# ProPrj_Pico_Pi_W_2024-12-25.net
KiCad netlist of a schematic drawn in EasyEDA Pro
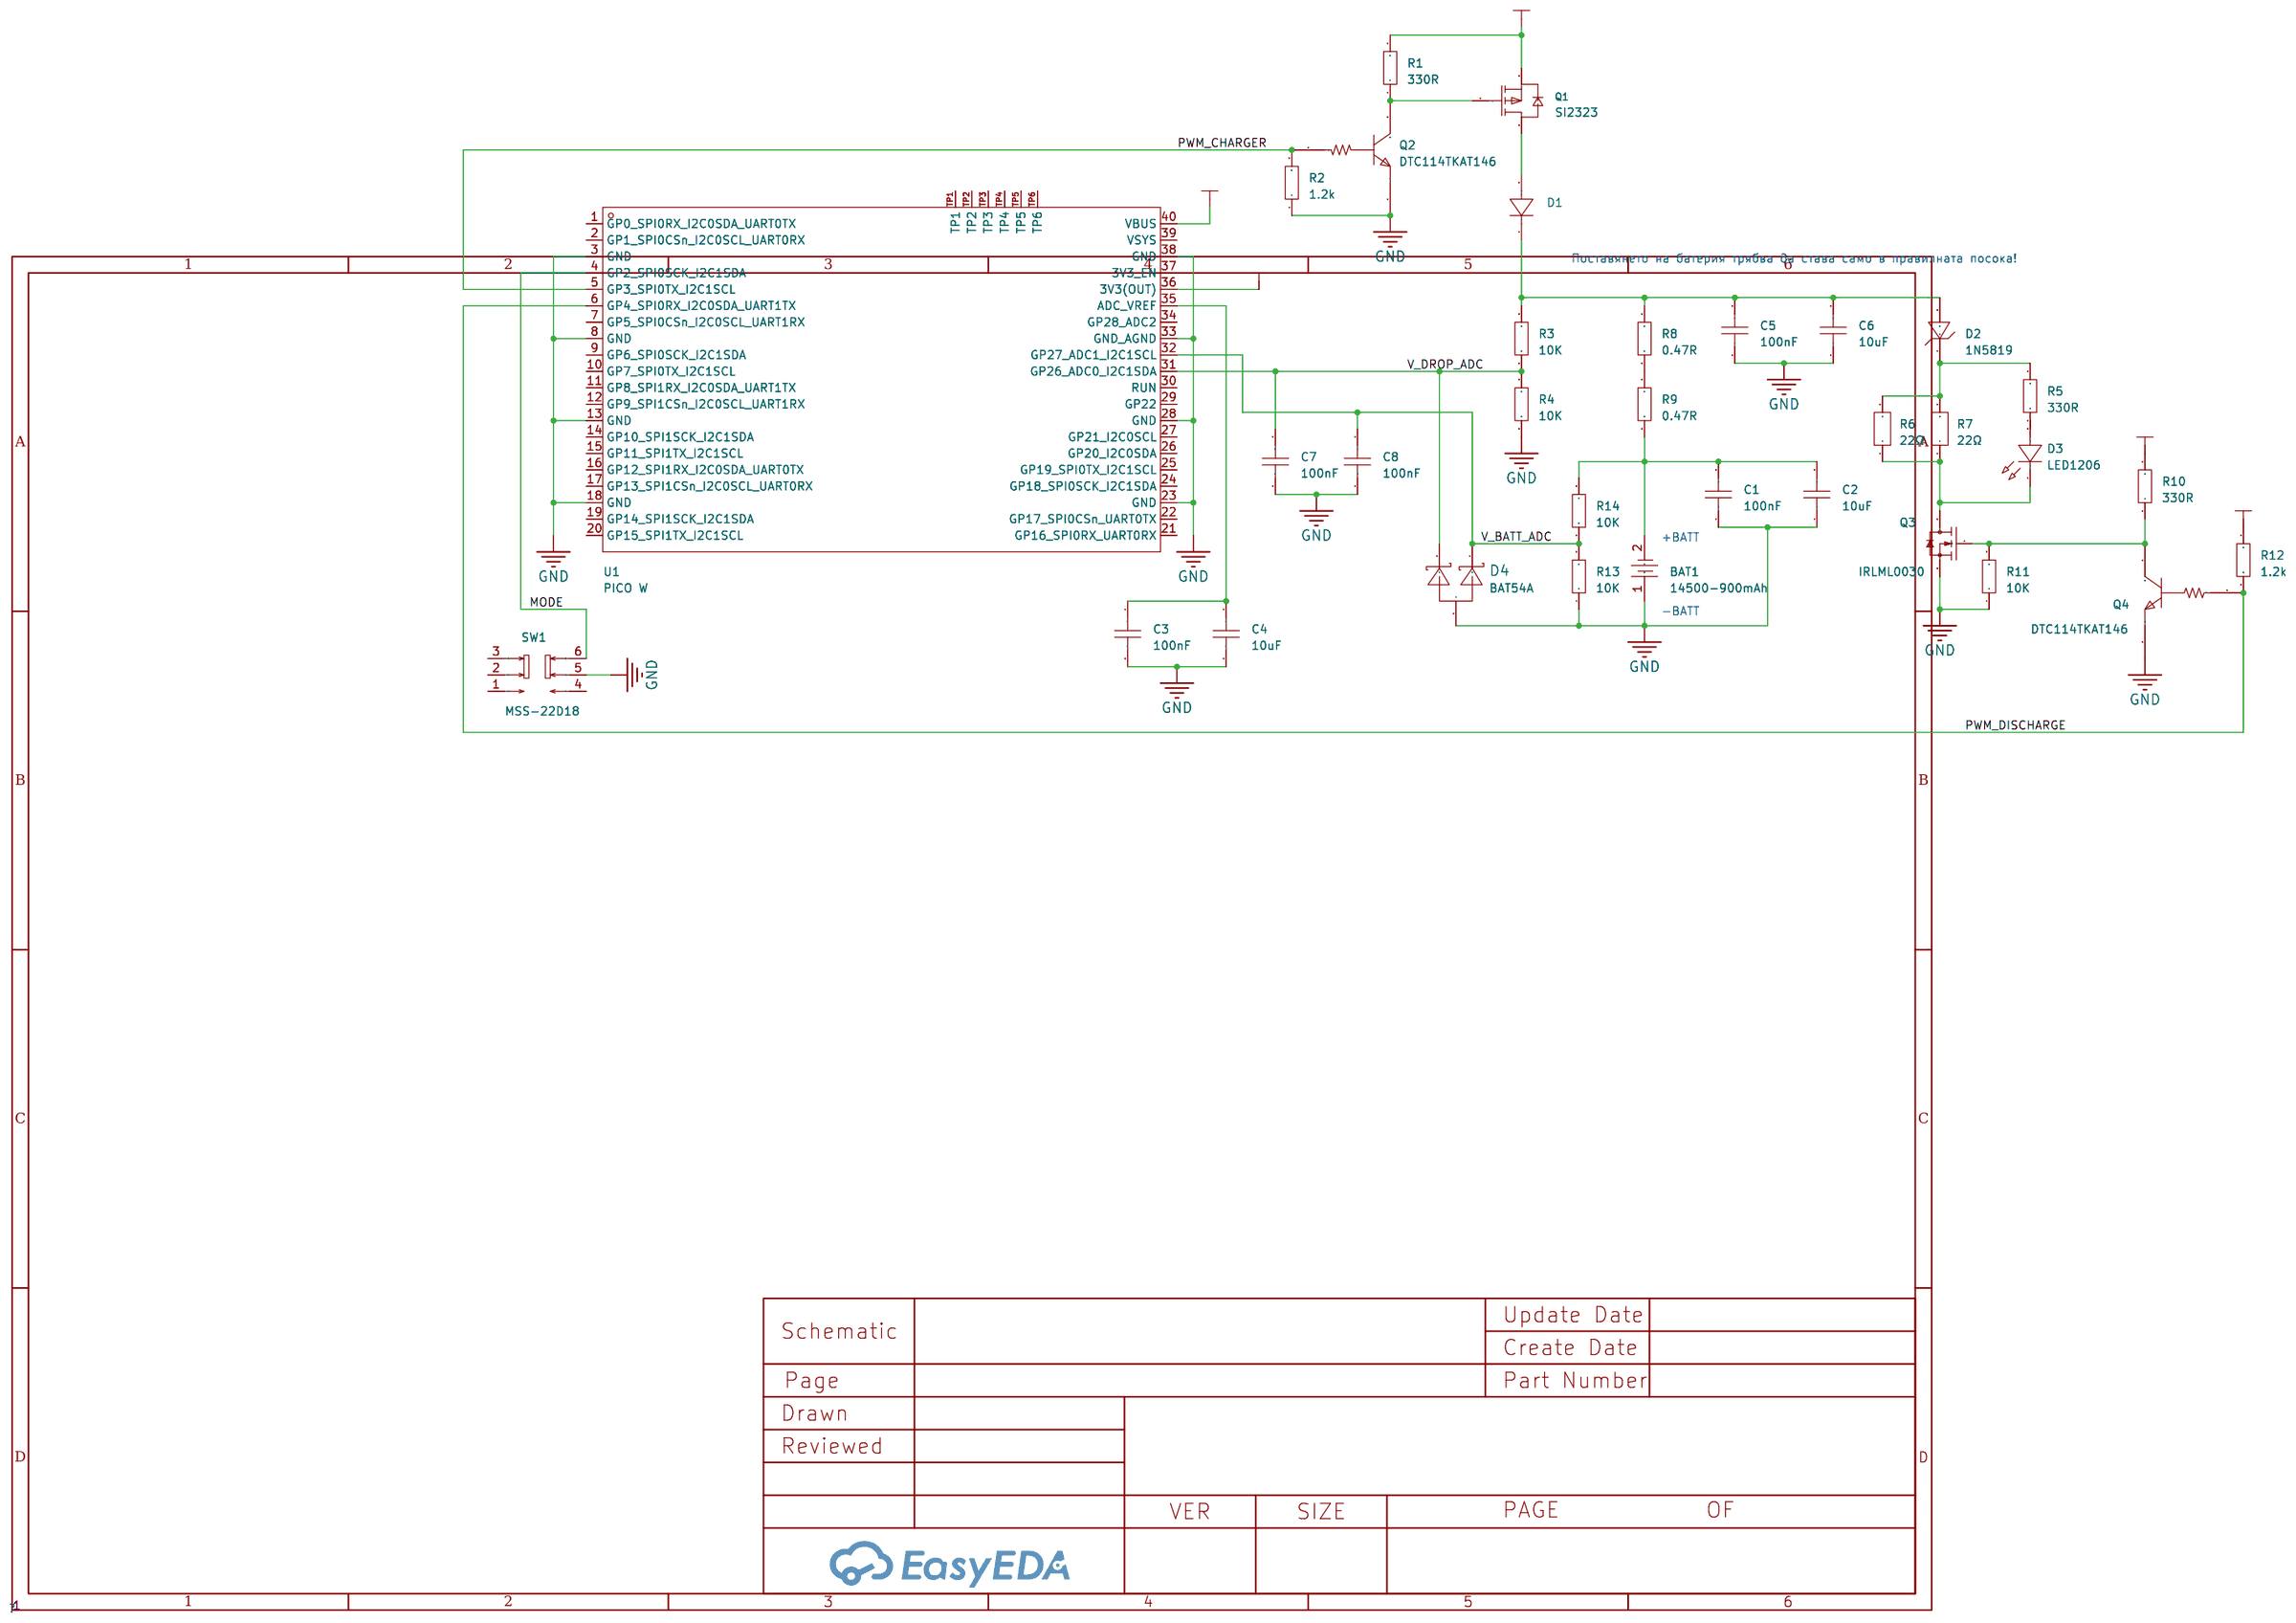
[diagram p0: schematic sheet]

(export (version "E")
  (design (tool "Eeschema 10.0.6"))
  (components
    (comp (ref "BAT1")
      (value "14500-900mAh")
      (footprint "easyedapro:BAT-TH_FLY-ER14250-1200MAH-01")
      (fields (field (name "Manufacturer") "FLYOUNG(远阳)"))
      (libsource (lib "easyedapro") (part "FLY-ER14250-1200MAH-01"))
    )
    (comp (ref "C1")
      (value "100nF")
      (footprint "easyedapro:C0805")
      (libsource (lib "easyedapro") (part "CAP"))
    )
    (comp (ref "C2")
      (value "10uF")
      (footprint "easyedapro:C0805")
      (libsource (lib "easyedapro") (part "CAP"))
    )
    (comp (ref "C3")
      (value "100nF")
      (footprint "easyedapro:C0805")
      (libsource (lib "easyedapro") (part "CAP"))
    )
    (comp (ref "C4")
      (value "10uF")
      (footprint "easyedapro:C0805")
      (libsource (lib "easyedapro") (part "CAP"))
    )
    (comp (ref "C5")
      (value "100nF")
      (footprint "easyedapro:C0805")
      (libsource (lib "easyedapro") (part "CAP"))
    )
    (comp (ref "C6")
      (value "10uF")
      (footprint "easyedapro:C0805")
      (libsource (lib "easyedapro") (part "CAP"))
    )
    (comp (ref "C7")
      (value "100nF")
      (footprint "easyedapro:C0805")
      (libsource (lib "easyedapro") (part "CAP"))
    )
    (comp (ref "C8")
      (value "100nF")
      (footprint "easyedapro:C0805")
      (libsource (lib "easyedapro") (part "CAP"))
    )
    (comp (ref "D1")
      (value "~")
      (footprint "easyedapro:SMA_L4.4-W2.8-LS5.4-RD")
      (libsource (lib "easyedapro") (part "D_1N4007"))
    )
    (comp (ref "D2")
      (value "1N5819")
      (footprint "easyedapro:DO-41_BD2.4-L4.7-P8.70-D0.9-RD")
      (description "Forward Voltage (Vf@If):600mV@1A Reverse Voltage (Vr):40V Average Rectified Current (Io):1A")
      (fields (field (name "Manufacturer") "银河微电子"))
      (libsource (lib "easyedapro") (part "1N5819_C393567"))
    )
    (comp (ref "D3")
      (value "LED1206")
      (footprint "easyedapro:LED1206-RD")
      (libsource (lib "easyedapro") (part "LED1206"))
    )
    (comp (ref "D4")
      (value "BAT54A")
      (footprint "easyedapro:SOT-23-3_L2.9-W1.3-P1.90-LS2.4-BR")
      (description "Forward Voltage (Vf@If):800mV@100mA Reverse Voltage (Vr):30V Average Rectified Current (Io):200mA")
      (fields (field (name "Manufacturer") "HT(金誉)"))
      (libsource (lib "easyedapro") (part "BAT54A_C179724"))
    )
    (comp (ref "Q1")
      (value "SI2323")
      (footprint "easyedapro:SOT-23-3_L2.9-W1.3-P0.95-LS2.4-BR")
      (fields (field (name "Manufacturer") "PAKER(派克微)"))
      (libsource (lib "easyedapro") (part "SI2323"))
    )
    (comp (ref "Q2")
      (value "DTC114TKAT146")
      (footprint "easyedapro:SOT-346_L2.9-W1.6-P1.90-LS2.8-TR-CW")
      (fields (field (name "Manufacturer") "ROHM(罗姆)"))
      (libsource (lib "easyedapro") (part "DTC114TKAT146"))
    )
    (comp (ref "Q3")
      (value "IRLML0030")
      (footprint "easyedapro:SOT-23-3_L2.9-W1.3-P1.90-LS2.4-BR")
      (fields (field (name "Manufacturer") "Leiditech(雷卯电子)"))
      (libsource (lib "easyedapro") (part "IRLML0030"))
    )
    (comp (ref "Q4")
      (value "DTC114TKAT146")
      (footprint "easyedapro:SOT-346_L2.9-W1.6-P1.90-LS2.8-TR-CW")
      (fields (field (name "Manufacturer") "ROHM(罗姆)"))
      (libsource (lib "easyedapro") (part "DTC114TKAT146"))
    )
    (comp (ref "R1")
      (value "330R")
      (footprint "easyedapro:R0603")
      (libsource (lib "easyedapro") (part "Res"))
    )
    (comp (ref "R2")
      (value "1.2k")
      (footprint "easyedapro:R0603")
      (libsource (lib "easyedapro") (part "Res"))
    )
    (comp (ref "R3") (value "10K") (footprint "easyedapro:R0603") (libsource (lib "easyedapro") (part "Res")))
    (comp (ref "R4") (value "10K") (footprint "easyedapro:R0603") (libsource (lib "easyedapro") (part "Res")))
    (comp (ref "R5")
      (value "330R")
      (footprint "easyedapro:R0603")
      (libsource (lib "easyedapro") (part "Res"))
    )
    (comp (ref "R6")
      (value "22Ω")
      (footprint "easyedapro:RES-TH_BD8.5-L24.5-P28.5-D0.7")
      (fields (field (name "Manufacturer Part") "FKN500JR-91-15R") (field (name "Manufacturer") "YAGEO(国巨)"))
      (libsource (lib "easyedapro") (part "FKN500JR-91-15R"))
    )
    (comp (ref "R7")
      (value "22Ω")
      (footprint "easyedapro:RES-TH_BD8.5-L24.5-P28.5-D0.7")
      (fields (field (name "Manufacturer Part") "FKN500JR-91-15R") (field (name "Manufacturer") "YAGEO(国巨)"))
      (libsource (lib "easyedapro") (part "FKN500JR-91-15R"))
    )
    (comp (ref "R8")
      (value "0.47R")
      (footprint "easyedapro:R0603")
      (libsource (lib "easyedapro") (part "Res"))
    )
    (comp (ref "R9")
      (value "0.47R")
      (footprint "easyedapro:R0603")
      (libsource (lib "easyedapro") (part "Res"))
    )
    (comp (ref "R10")
      (value "330R")
      (footprint "easyedapro:R0603")
      (libsource (lib "easyedapro") (part "Res"))
    )
    (comp (ref "R11")
      (value "10K")
      (footprint "easyedapro:R0603")
      (libsource (lib "easyedapro") (part "Res"))
    )
    (comp (ref "R12")
      (value "1.2k")
      (footprint "easyedapro:R0603")
      (libsource (lib "easyedapro") (part "Res"))
    )
    (comp (ref "R13")
      (value "10K")
      (footprint "easyedapro:R0603")
      (libsource (lib "easyedapro") (part "Res"))
    )
    (comp (ref "R14")
      (value "10K")
      (footprint "easyedapro:R0603")
      (libsource (lib "easyedapro") (part "Res"))
    )
    (comp (ref "SW1")
      (value "MSS-22D18")
      (footprint "easyedapro:SW-TH_MSS-22D18")
      (libsource (lib "easyedapro") (part "MSS-22D18(杆长2MM)"))
    )
    (comp (ref "U1")
      (value "PICO W")
      (footprint "easyedapro:COMM-SMD_L51.0-W21.0-P2.54_PICOW")
      (fields (field (name "Manufacturer") "Raspberry Pi(树莓派)"))
      (libsource (lib "easyedapro") (part "PICO W"))
    )
  )
  (nets
    (net (code "1") (name "+3V") (class "Default")
      (node (ref "R12") (pin "2") (pinfunction "2_2") (pintype "input"))
      (node (ref "U1") (pin "36") (pinfunction "3V3(OUT)_36") (pintype "unspecified"))
    )
    (net (code "2") (name "+5V") (class "Default")
      (node (ref "Q1") (pin "2") (pinfunction "S_2") (pintype "input"))
      (node (ref "R1") (pin "2") (pinfunction "2_2") (pintype "input"))
      (node (ref "R10") (pin "2") (pinfunction "2_2") (pintype "input"))
      (node (ref "U1") (pin "40") (pinfunction "VBUS_40") (pintype "unspecified"))
    )
    (net (code "3") (name "/MODE") (class "Default")
      (node (ref "SW1") (pin "6") (pinfunction "6_6") (pintype "unspecified"))
      (node (ref "U1") (pin "4") (pinfunction "GP2_SPI0SCK_I2C1SDA_4") (pintype "unspecified"))
    )
    (net (code "4") (name "/PWM_CHARGER") (class "Default")
      (node (ref "Q2") (pin "2") (pinfunction "B_2") (pintype "unspecified"))
      (node (ref "R2") (pin "2") (pinfunction "2_2") (pintype "input"))
      (node (ref "U1") (pin "5") (pinfunction "GP3_SPI0TX_I2C1SCL_5") (pintype "unspecified"))
    )
    (net (code "5") (name "/PWM_DISCHARGE") (class "Default")
      (node (ref "Q4") (pin "2") (pinfunction "B_2") (pintype "unspecified"))
      (node (ref "R12") (pin "1") (pinfunction "1_1") (pintype "input"))
      (node (ref "U1") (pin "6") (pinfunction "GP4_SPI0RX_I2C0SDA_UART1TX_6") (pintype "unspecified"))
    )
    (net (code "6") (name "/V_BATT_ADC") (class "Default")
      (node (ref "C8") (pin "2") (pinfunction "2_2") (pintype "input"))
      (node (ref "D4") (pin "1") (pinfunction "A_1") (pintype "input"))
      (node (ref "R13") (pin "2") (pinfunction "2_2") (pintype "input"))
      (node (ref "R14") (pin "1") (pinfunction "1_1") (pintype "input"))
      (node (ref "U1") (pin "32") (pinfunction "GP27_ADC1_I2C1SCL_32") (pintype "unspecified"))
    )
    (net (code "7") (name "/V_DROP_ADC") (class "Default")
      (node (ref "C7") (pin "2") (pinfunction "2_2") (pintype "input"))
      (node (ref "D4") (pin "2") (pinfunction "A_2") (pintype "input"))
      (node (ref "R3") (pin "1") (pinfunction "1_1") (pintype "input"))
      (node (ref "R4") (pin "2") (pinfunction "2_2") (pintype "input"))
      (node (ref "U1") (pin "31") (pinfunction "GP26_ADC0_I2C1SDA_31") (pintype "unspecified"))
    )
    (net (code "8") (name "GND") (class "Default")
      (node (ref "BAT1") (pin "1") (pinfunction "1_1") (pintype "input"))
      (node (ref "C1") (pin "1") (pinfunction "1_1") (pintype "input"))
      (node (ref "C2") (pin "1") (pinfunction "1_1") (pintype "input"))
      (node (ref "C3") (pin "2") (pinfunction "2_2") (pintype "input"))
      (node (ref "C4") (pin "2") (pinfunction "2_2") (pintype "input"))
      (node (ref "C5") (pin "1") (pinfunction "1_1") (pintype "input"))
      (node (ref "C6") (pin "1") (pinfunction "1_1") (pintype "input"))
      (node (ref "C7") (pin "1") (pinfunction "1_1") (pintype "input"))
      (node (ref "C8") (pin "1") (pinfunction "1_1") (pintype "input"))
      (node (ref "D4") (pin "3") (pinfunction "K_3") (pintype "input"))
      (node (ref "Q2") (pin "1") (pinfunction "E_1") (pintype "unspecified"))
      (node (ref "Q3") (pin "2") (pinfunction "S_2") (pintype "unspecified"))
      (node (ref "Q4") (pin "1") (pinfunction "E_1") (pintype "unspecified"))
      (node (ref "R11") (pin "1") (pinfunction "1_1") (pintype "input"))
      (node (ref "R13") (pin "1") (pinfunction "1_1") (pintype "input"))
      (node (ref "R2") (pin "1") (pinfunction "1_1") (pintype "input"))
      (node (ref "R4") (pin "1") (pinfunction "1_1") (pintype "input"))
      (node (ref "SW1") (pin "5") (pinfunction "5_5") (pintype "unspecified"))
      (node (ref "U1") (pin "13") (pinfunction "GND_13") (pintype "unspecified"))
      (node (ref "U1") (pin "18") (pinfunction "GND_18") (pintype "unspecified"))
      (node (ref "U1") (pin "23") (pinfunction "GND_23") (pintype "unspecified"))
      (node (ref "U1") (pin "28") (pinfunction "GND_28") (pintype "unspecified"))
      (node (ref "U1") (pin "3") (pinfunction "GND_3") (pintype "unspecified"))
      (node (ref "U1") (pin "33") (pinfunction "GND_AGND_33") (pintype "unspecified"))
      (node (ref "U1") (pin "38") (pinfunction "GND_38") (pintype "unspecified"))
      (node (ref "U1") (pin "8") (pinfunction "GND_8") (pintype "unspecified"))
    )
    (net (code "9") (name "Net-(BAT1-Pad2)") (class "Default")
      (node (ref "BAT1") (pin "2") (pinfunction "2_2") (pintype "input"))
      (node (ref "C1") (pin "2") (pinfunction "2_2") (pintype "input"))
      (node (ref "C2") (pin "2") (pinfunction "2_2") (pintype "input"))
      (node (ref "R14") (pin "2") (pinfunction "2_2") (pintype "input"))
      (node (ref "R9") (pin "1") (pinfunction "1_1") (pintype "input"))
    )
    (net (code "10") (name "Net-(D1-A)") (class "Default")
      (node (ref "D1") (pin "2") (pinfunction "A_2") (pintype "input"))
      (node (ref "Q1") (pin "3") (pinfunction "D_3") (pintype "input"))
    )
    (net (code "11") (name "Net-(D1-K)") (class "Default")
      (node (ref "C5") (pin "2") (pinfunction "2_2") (pintype "input"))
      (node (ref "C6") (pin "2") (pinfunction "2_2") (pintype "input"))
      (node (ref "D1") (pin "1") (pinfunction "K_1") (pintype "input"))
      (node (ref "D2") (pin "2") (pinfunction "A_2") (pintype "unspecified"))
      (node (ref "R3") (pin "2") (pinfunction "2_2") (pintype "input"))
      (node (ref "R8") (pin "1") (pinfunction "1_1") (pintype "input"))
    )
    (net (code "12") (name "Net-(D2-C)") (class "Default")
      (node (ref "D2") (pin "1") (pinfunction "C_1") (pintype "unspecified"))
      (node (ref "R5") (pin "2") (pinfunction "2_2") (pintype "input"))
      (node (ref "R6") (pin "2") (pinfunction "2_2") (pintype "unspecified"))
      (node (ref "R7") (pin "2") (pinfunction "2_2") (pintype "unspecified"))
    )
    (net (code "13") (name "Net-(D3-A)") (class "Default")
      (node (ref "D3") (pin "2") (pinfunction "A_2") (pintype "input"))
      (node (ref "R5") (pin "1") (pinfunction "1_1") (pintype "input"))
    )
    (net (code "14") (name "Net-(D3-K)") (class "Default")
      (node (ref "D3") (pin "1") (pinfunction "K_1") (pintype "input"))
      (node (ref "Q3") (pin "3") (pinfunction "D_3") (pintype "unspecified"))
      (node (ref "R6") (pin "1") (pinfunction "1_1") (pintype "unspecified"))
      (node (ref "R7") (pin "1") (pinfunction "1_1") (pintype "unspecified"))
    )
    (net (code "15") (name "Net-(Q1-G)") (class "Default")
      (node (ref "Q1") (pin "1") (pinfunction "G_1") (pintype "input"))
      (node (ref "Q2") (pin "3") (pinfunction "C_3") (pintype "unspecified"))
      (node (ref "R1") (pin "1") (pinfunction "1_1") (pintype "input"))
    )
    (net (code "16") (name "Net-(Q3-G)") (class "Default")
      (node (ref "Q3") (pin "1") (pinfunction "G_1") (pintype "unspecified"))
      (node (ref "Q4") (pin "3") (pinfunction "C_3") (pintype "unspecified"))
      (node (ref "R10") (pin "1") (pinfunction "1_1") (pintype "input"))
      (node (ref "R11") (pin "2") (pinfunction "2_2") (pintype "input"))
    )
    (net (code "17") (name "Net-(R8-Pad2)") (class "Default")
      (node (ref "R8") (pin "2") (pinfunction "2_2") (pintype "input"))
      (node (ref "R9") (pin "2") (pinfunction "2_2") (pintype "input"))
    )
    (net (code "18") (name "Net-(U1-ADC_VREF)") (class "Default")
      (node (ref "C3") (pin "1") (pinfunction "1_1") (pintype "input"))
      (node (ref "C4") (pin "1") (pinfunction "1_1") (pintype "input"))
      (node (ref "U1") (pin "35") (pinfunction "ADC_VREF_35") (pintype "unspecified"))
    )
    (net (code "19") (name "unconnected-(SW1-Pad1)") (class "Default")
      (node (ref "SW1") (pin "1") (pinfunction "1_1") (pintype "unspecified"))
    )
    (net (code "20") (name "unconnected-(SW1-Pad2)") (class "Default")
      (node (ref "SW1") (pin "2") (pinfunction "2_2") (pintype "unspecified"))
    )
    (net (code "21") (name "unconnected-(SW1-Pad3)") (class "Default")
      (node (ref "SW1") (pin "3") (pinfunction "3_3") (pintype "unspecified"))
    )
    (net (code "22") (name "unconnected-(SW1-Pad4)") (class "Default")
      (node (ref "SW1") (pin "4") (pinfunction "4_4") (pintype "unspecified"))
    )
    (net (code "23") (name "unconnected-(U1-3V3_EN-Pad37)") (class "Default")
      (node (ref "U1") (pin "37") (pinfunction "3V3_EN_37") (pintype "unspecified"))
    )
    (net (code "24") (name "unconnected-(U1-GP0_SPI0RX_I2C0SDA_UART0TX-Pad1)") (class "Default")
      (node (ref "U1") (pin "1") (pinfunction "GP0_SPI0RX_I2C0SDA_UART0TX_1") (pintype "unspecified"))
    )
    (net (code "25") (name "unconnected-(U1-GP1_SPI0CSn_I2C0SCL_UART0RX-Pad2)") (class "Default")
      (node (ref "U1") (pin "2") (pinfunction "GP1_SPI0CSn_I2C0SCL_UART0RX_2") (pintype "unspecified"))
    )
    (net (code "26") (name "unconnected-(U1-GP5_SPI0CSn_I2C0SCL_UART1RX-Pad7)") (class "Default")
      (node (ref "U1") (pin "7") (pinfunction "GP5_SPI0CSn_I2C0SCL_UART1RX_7") (pintype "unspecified"))
    )
    (net (code "27") (name "unconnected-(U1-GP6_SPI0SCK_I2C1SDA-Pad9)") (class "Default")
      (node (ref "U1") (pin "9") (pinfunction "GP6_SPI0SCK_I2C1SDA_9") (pintype "unspecified"))
    )
    (net (code "28") (name "unconnected-(U1-GP7_SPI0TX_I2C1SCL-Pad10)") (class "Default")
      (node (ref "U1") (pin "10") (pinfunction "GP7_SPI0TX_I2C1SCL_10") (pintype "unspecified"))
    )
    (net (code "29") (name "unconnected-(U1-GP8_SPI1RX_I2C0SDA_UART1TX-Pad11)") (class "Default")
      (node (ref "U1") (pin "11") (pinfunction "GP8_SPI1RX_I2C0SDA_UART1TX_11") (pintype "unspecified"))
    )
    (net (code "30") (name "unconnected-(U1-GP9_SPI1CSn_I2C0SCL_UART1RX-Pad12)") (class "Default")
      (node (ref "U1") (pin "12") (pinfunction "GP9_SPI1CSn_I2C0SCL_UART1RX_12") (pintype "unspecified"))
    )
    (net (code "31") (name "unconnected-(U1-GP10_SPI1SCK_I2C1SDA-Pad14)") (class "Default")
      (node (ref "U1") (pin "14") (pinfunction "GP10_SPI1SCK_I2C1SDA_14") (pintype "unspecified"))
    )
    (net (code "32") (name "unconnected-(U1-GP11_SPI1TX_I2C1SCL-Pad15)") (class "Default")
      (node (ref "U1") (pin "15") (pinfunction "GP11_SPI1TX_I2C1SCL_15") (pintype "unspecified"))
    )
    (net (code "33") (name "unconnected-(U1-GP12_SPI1RX_I2C0SDA_UART0TX-Pad16)") (class "Default")
      (node (ref "U1") (pin "16") (pinfunction "GP12_SPI1RX_I2C0SDA_UART0TX_16") (pintype "unspecified"))
    )
    (net (code "34") (name "unconnected-(U1-GP13_SPI1CSn_I2C0SCL_UART0RX-Pad17)") (class "Default")
      (node (ref "U1") (pin "17") (pinfunction "GP13_SPI1CSn_I2C0SCL_UART0RX_17") (pintype "unspecified"))
    )
    (net (code "35") (name "unconnected-(U1-GP14_SPI1SCK_I2C1SDA-Pad19)") (class "Default")
      (node (ref "U1") (pin "19") (pinfunction "GP14_SPI1SCK_I2C1SDA_19") (pintype "unspecified"))
    )
    (net (code "36") (name "unconnected-(U1-GP15_SPI1TX_I2C1SCL-Pad20)") (class "Default")
      (node (ref "U1") (pin "20") (pinfunction "GP15_SPI1TX_I2C1SCL_20") (pintype "unspecified"))
    )
    (net (code "37") (name "unconnected-(U1-GP16_SPI0RX_UART0RX-Pad21)") (class "Default")
      (node (ref "U1") (pin "21") (pinfunction "GP16_SPI0RX_UART0RX_21") (pintype "unspecified"))
    )
    (net (code "38") (name "unconnected-(U1-GP17_SPI0CSn_UART0TX-Pad22)") (class "Default")
      (node (ref "U1") (pin "22") (pinfunction "GP17_SPI0CSn_UART0TX_22") (pintype "unspecified"))
    )
    (net (code "39") (name "unconnected-(U1-GP18_SPI0SCK_I2C1SDA-Pad24)") (class "Default")
      (node (ref "U1") (pin "24") (pinfunction "GP18_SPI0SCK_I2C1SDA_24") (pintype "unspecified"))
    )
    (net (code "40") (name "unconnected-(U1-GP19_SPI0TX_I2C1SCL-Pad25)") (class "Default")
      (node (ref "U1") (pin "25") (pinfunction "GP19_SPI0TX_I2C1SCL_25") (pintype "unspecified"))
    )
    (net (code "41") (name "unconnected-(U1-GP20_I2C0SDA-Pad26)") (class "Default")
      (node (ref "U1") (pin "26") (pinfunction "GP20_I2C0SDA_26") (pintype "unspecified"))
    )
    (net (code "42") (name "unconnected-(U1-GP21_I2C0SCL-Pad27)") (class "Default")
      (node (ref "U1") (pin "27") (pinfunction "GP21_I2C0SCL_27") (pintype "unspecified"))
    )
    (net (code "43") (name "unconnected-(U1-GP22-Pad29)") (class "Default")
      (node (ref "U1") (pin "29") (pinfunction "GP22_29") (pintype "unspecified"))
    )
    (net (code "44") (name "unconnected-(U1-GP28_ADC2-Pad34)") (class "Default")
      (node (ref "U1") (pin "34") (pinfunction "GP28_ADC2_34") (pintype "unspecified"))
    )
    (net (code "45") (name "unconnected-(U1-PadTP1)") (class "Default")
      (node (ref "U1") (pin "TP1") (pinfunction "TP1_TP1") (pintype "unspecified"))
    )
    (net (code "46") (name "unconnected-(U1-PadTP2)") (class "Default")
      (node (ref "U1") (pin "TP2") (pinfunction "TP2_TP2") (pintype "unspecified"))
    )
    (net (code "47") (name "unconnected-(U1-PadTP3)") (class "Default")
      (node (ref "U1") (pin "TP3") (pinfunction "TP3_TP3") (pintype "unspecified"))
    )
    (net (code "48") (name "unconnected-(U1-PadTP4)") (class "Default")
      (node (ref "U1") (pin "TP4") (pinfunction "TP4_TP4") (pintype "unspecified"))
    )
    (net (code "49") (name "unconnected-(U1-PadTP5)") (class "Default")
      (node (ref "U1") (pin "TP5") (pinfunction "TP5_TP5") (pintype "unspecified"))
    )
    (net (code "50") (name "unconnected-(U1-PadTP6)") (class "Default")
      (node (ref "U1") (pin "TP6") (pinfunction "TP6_TP6") (pintype "unspecified"))
    )
    (net (code "51") (name "unconnected-(U1-RUN-Pad30)") (class "Default")
      (node (ref "U1") (pin "30") (pinfunction "RUN_30") (pintype "unspecified"))
    )
    (net (code "52") (name "unconnected-(U1-VSYS-Pad39)") (class "Default")
      (node (ref "U1") (pin "39") (pinfunction "VSYS_39") (pintype "unspecified"))
    )
  )
)
